# sensor.net
KiCad netlist of a schematic drawn in Altium Designer
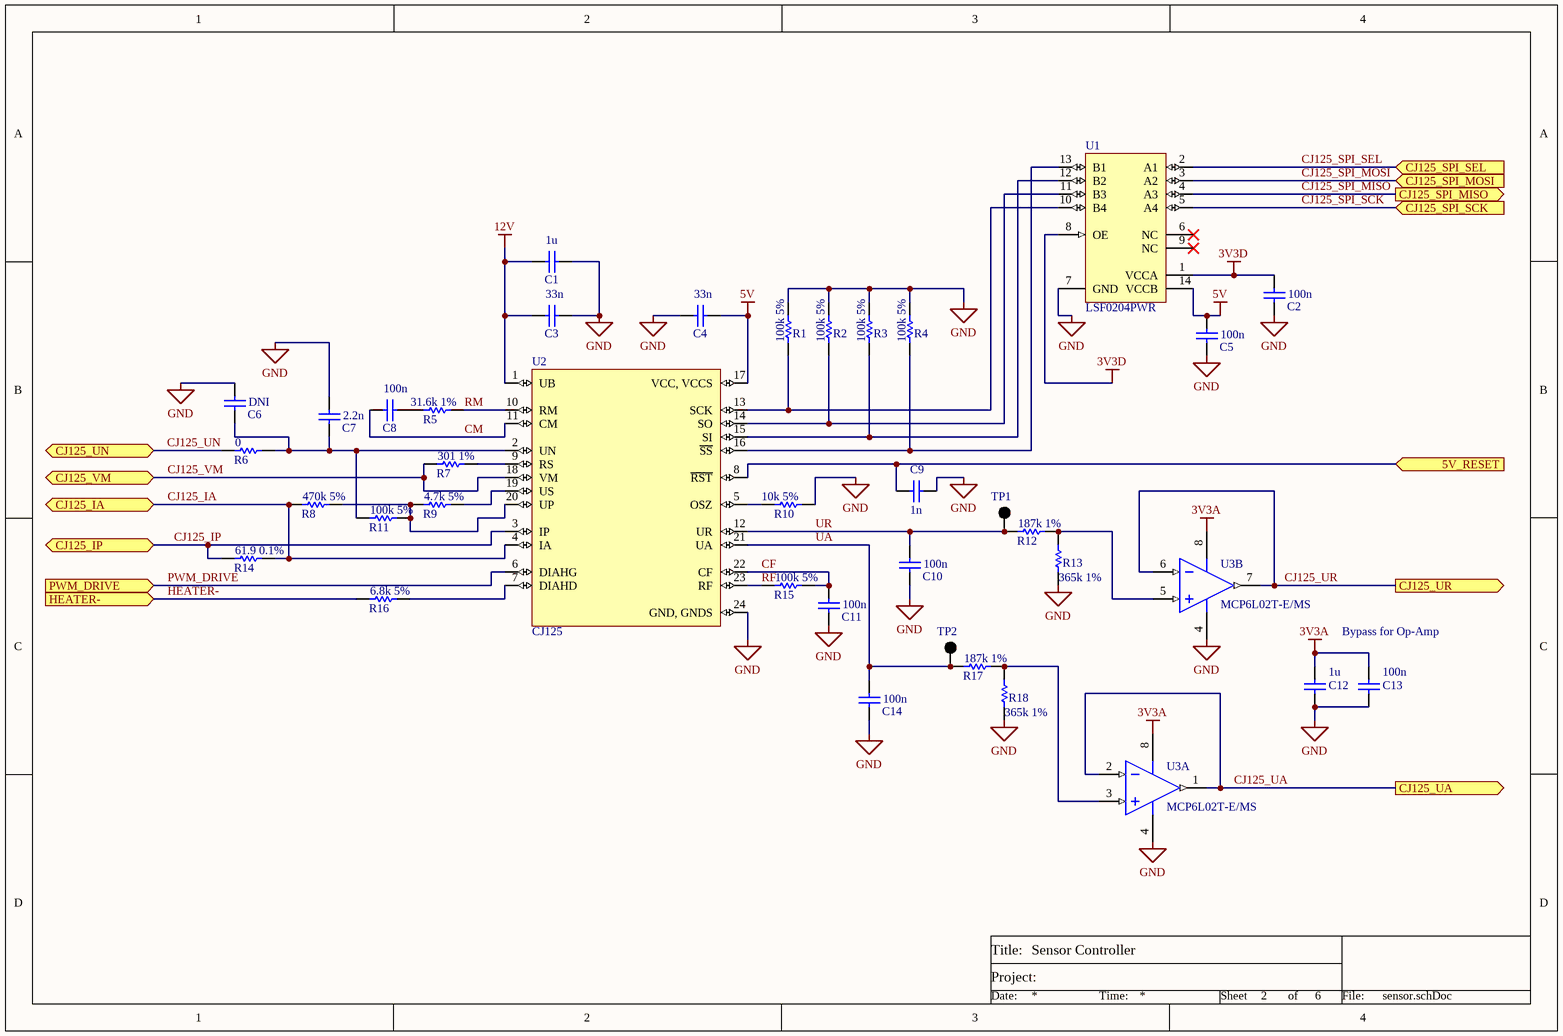
[diagram p0: sensor.schDoc]

(export (version "E")
  (design (tool "Eeschema 10.0.6"))
  (components
    (comp (ref "C1")
      (value "1u")
      (footprint "0805")
      (description "Generic 0805 Capacitor")
      (libsource (lib "symbol_library") (part "C_0805"))
    )
    (comp (ref "C2")
      (value "100n")
      (footprint "0805")
      (description "Generic 0805 Capacitor")
      (libsource (lib "symbol_library") (part "C_0805"))
    )
    (comp (ref "C3")
      (value "33n")
      (footprint "0805")
      (description "Generic 0805 Capacitor")
      (libsource (lib "symbol_library") (part "C_0805"))
    )
    (comp (ref "C4")
      (value "33n")
      (footprint "0805")
      (description "Generic 0805 Capacitor")
      (libsource (lib "symbol_library") (part "C_0805"))
    )
    (comp (ref "C5")
      (value "100n")
      (footprint "0805")
      (description "Generic 0805 Capacitor")
      (libsource (lib "symbol_library") (part "C_0805"))
    )
    (comp (ref "C6")
      (value "DNI")
      (footprint "0805")
      (description "Generic 0805 Capacitor")
      (libsource (lib "symbol_library") (part "C_0805"))
    )
    (comp (ref "C7")
      (value "2.2n")
      (footprint "0805")
      (description "Generic 0805 Capacitor")
      (libsource (lib "symbol_library") (part "C_0805"))
    )
    (comp (ref "C8")
      (value "100n")
      (footprint "0805")
      (description "Generic 0805 Capacitor")
      (libsource (lib "symbol_library") (part "C_0805"))
    )
    (comp (ref "C9")
      (value "1n")
      (footprint "0805")
      (description "Generic 0805 Capacitor")
      (libsource (lib "symbol_library") (part "C_0805"))
    )
    (comp (ref "C10")
      (value "100n")
      (footprint "0805")
      (description "Generic 0805 Capacitor")
      (libsource (lib "symbol_library") (part "C_0805"))
    )
    (comp (ref "C11")
      (value "100n")
      (footprint "0805")
      (description "Generic 0805 Capacitor")
      (libsource (lib "symbol_library") (part "C_0805"))
    )
    (comp (ref "C12")
      (value "1u")
      (footprint "0805")
      (description "Generic 0805 Capacitor")
      (libsource (lib "symbol_library") (part "C_0805"))
    )
    (comp (ref "C13")
      (value "100n")
      (footprint "0805")
      (description "Generic 0805 Capacitor")
      (libsource (lib "symbol_library") (part "C_0805"))
    )
    (comp (ref "C14")
      (value "100n")
      (footprint "0805")
      (description "Generic 0805 Capacitor")
      (libsource (lib "symbol_library") (part "C_0805"))
    )
    (comp (ref "R1")
      (value "100k 5%")
      (footprint "0603")
      (description "Generic 0603 Resistor")
      (libsource (lib "symbol_library") (part "R_0603"))
    )
    (comp (ref "R2")
      (value "100k 5%")
      (footprint "0603")
      (description "Generic 0603 Resistor")
      (libsource (lib "symbol_library") (part "R_0603"))
    )
    (comp (ref "R3")
      (value "100k 5%")
      (footprint "0603")
      (description "Generic 0603 Resistor")
      (libsource (lib "symbol_library") (part "R_0603"))
    )
    (comp (ref "R4")
      (value "100k 5%")
      (footprint "0603")
      (description "Generic 0603 Resistor")
      (libsource (lib "symbol_library") (part "R_0603"))
    )
    (comp (ref "R5")
      (value "31.6k 1%")
      (footprint "0603")
      (description "Generic 0603 Resistor")
      (libsource (lib "symbol_library") (part "R_0603"))
    )
    (comp (ref "R6")
      (value "0")
      (footprint "0603")
      (description "Generic 0603 Resistor")
      (libsource (lib "symbol_library") (part "R_0603"))
    )
    (comp (ref "R7")
      (value "301 1%")
      (footprint "0603")
      (description "Generic 0603 Resistor")
      (libsource (lib "symbol_library") (part "R_0603"))
    )
    (comp (ref "R8")
      (value "470k 5%")
      (footprint "0603")
      (description "Generic 0603 Resistor")
      (libsource (lib "symbol_library") (part "R_0603"))
    )
    (comp (ref "R9")
      (value "4.7k 5%")
      (footprint "0603")
      (description "Generic 0603 Resistor")
      (libsource (lib "symbol_library") (part "R_0603"))
    )
    (comp (ref "R10")
      (value "10k 5%")
      (footprint "0603")
      (description "Generic 0603 Resistor")
      (libsource (lib "symbol_library") (part "R_0603"))
    )
    (comp (ref "R11")
      (value "100k 5%")
      (footprint "0603")
      (description "Generic 0603 Resistor")
      (libsource (lib "symbol_library") (part "R_0603"))
    )
    (comp (ref "R12")
      (value "187k 1%")
      (footprint "0603")
      (description "Generic 0603 Resistor")
      (libsource (lib "symbol_library") (part "R_0603"))
    )
    (comp (ref "R13")
      (value "365k 1%")
      (footprint "0603")
      (description "Generic 0603 Resistor")
      (libsource (lib "symbol_library") (part "R_0603"))
    )
    (comp (ref "R14")
      (value "61.9 0.1%")
      (footprint "0603")
      (description "Generic 0603 Resistor")
      (libsource (lib "symbol_library") (part "R_0603"))
    )
    (comp (ref "R15")
      (value "100k 5%")
      (footprint "0603")
      (description "Generic 0603 Resistor")
      (libsource (lib "symbol_library") (part "R_0603"))
    )
    (comp (ref "R16")
      (value "6.8k 5%")
      (footprint "0603")
      (description "Generic 0603 Resistor")
      (libsource (lib "symbol_library") (part "R_0603"))
    )
    (comp (ref "R17")
      (value "187k 1%")
      (footprint "0603")
      (description "Generic 0603 Resistor")
      (libsource (lib "symbol_library") (part "R_0603"))
    )
    (comp (ref "R18")
      (value "365k 1%")
      (footprint "0603")
      (description "Generic 0603 Resistor")
      (libsource (lib "symbol_library") (part "R_0603"))
    )
    (comp (ref "TP1")
      (value "5001")
      (footprint "KSTN-5001")
      (description "Test Point, Black, 1-Pin THD, RoHS, Bulk")
      (fields (field (name "MANUFACTURER") "Keystone"))
      (libsource (lib "symbol_library") (part "TP5001"))
    )
    (comp (ref "TP2")
      (value "5001")
      (footprint "KSTN-5001")
      (description "Test Point, Black, 1-Pin THD, RoHS, Bulk")
      (fields (field (name "MANUFACTURER") "Keystone"))
      (libsource (lib "symbol_library") (part "TP5001"))
    )
    (comp (ref "U1")
      (value "LSF0204PWR")
      (footprint "PW0014A_M")
      (fields (field (name "MANUFACTURER") "Texas Instruments"))
      (libsource (lib "symbol_library") (part "LSF0204"))
    )
    (comp (ref "U2")
      (value "CJ125")
      (footprint "SOIC-24")
      (description "5V 2Mbaud SMT Lambda Probe Interface IC - SOIC-24")
      (libsource (lib "symbol_library") (part "CJ125"))
    )
    (comp (ref "U3")
      (value "MCP6L02T-E/MS")
      (footprint "MSOP8_M")
      (description "1 MHz, 85 渭A Dual Op Amp, 8-Pin MSOP, Extended Temperature Range, Tape and Reel")
      (libsource (lib "symbol_library") (part "MCP6L02"))
    )
  )
  (nets
    (net (code "1") (name "/5V_RESET") (class "Default")
      (node (ref "C9") (pin "1") (pinfunction "1_1") (pintype "passive"))
      (node (ref "U2") (pin "8") (pinfunction "~{RST}_8") (pintype "bidirectional"))
    )
    (net (code "2") (name "/CF") (class "Default")
      (node (ref "C11") (pin "2") (pinfunction "2_2") (pintype "passive"))
      (node (ref "R15") (pin "2") (pinfunction "2_2") (pintype "passive"))
      (node (ref "U2") (pin "22") (pinfunction "CF_22") (pintype "bidirectional"))
    )
    (net (code "3") (name "/CJ125_IA") (class "Default")
      (node (ref "R14") (pin "2") (pinfunction "2_2") (pintype "passive"))
      (node (ref "R8") (pin "1") (pinfunction "1_1") (pintype "passive"))
      (node (ref "U2") (pin "4") (pinfunction "IA_4") (pintype "bidirectional"))
    )
    (net (code "4") (name "/CJ125_IP") (class "Default")
      (node (ref "R14") (pin "1") (pinfunction "1_1") (pintype "passive"))
      (node (ref "U2") (pin "3") (pinfunction "IP_3") (pintype "bidirectional"))
    )
    (net (code "5") (name "/CJ125_SPI_MISO") (class "Default")
      (node (ref "U1") (pin "4") (pinfunction "A3_4") (pintype "bidirectional"))
    )
    (net (code "6") (name "/CJ125_SPI_MOSI") (class "Default")
      (node (ref "U1") (pin "3") (pinfunction "A2_3") (pintype "bidirectional"))
    )
    (net (code "7") (name "/CJ125_SPI_SCK") (class "Default")
      (node (ref "U1") (pin "5") (pinfunction "A4_5") (pintype "bidirectional"))
    )
    (net (code "8") (name "/CJ125_SPI_SEL") (class "Default")
      (node (ref "U1") (pin "2") (pinfunction "A1_2") (pintype "bidirectional"))
    )
    (net (code "9") (name "/CJ125_UA") (class "Default")
      (node (ref "U3") (pin "1") (pinfunction "VOUTA_1") (pintype "output"))
      (node (ref "U3") (pin "2") (pinfunction "VINA-_2") (pintype "input"))
    )
    (net (code "10") (name "/CJ125_UN") (class "Default")
      (node (ref "R6") (pin "1") (pinfunction "1_1") (pintype "passive"))
    )
    (net (code "11") (name "/CJ125_UR") (class "Default")
      (node (ref "U3") (pin "6") (pinfunction "VINB-_6") (pintype "input"))
      (node (ref "U3") (pin "7") (pinfunction "VOUTB_7") (pintype "output"))
    )
    (net (code "12") (name "/CJ125_VM") (class "Default")
      (node (ref "R7") (pin "1") (pinfunction "1_1") (pintype "passive"))
      (node (ref "U2") (pin "18") (pinfunction "VM_18") (pintype "bidirectional"))
    )
    (net (code "13") (name "/CM") (class "Default")
      (node (ref "C8") (pin "1") (pinfunction "1_1") (pintype "passive"))
      (node (ref "U2") (pin "11") (pinfunction "CM_11") (pintype "bidirectional"))
    )
    (net (code "14") (name "/HEATER-") (class "Default")
      (node (ref "R16") (pin "1") (pinfunction "1_1") (pintype "passive"))
    )
    (net (code "15") (name "/PWM_DRIVE") (class "Default")
      (node (ref "U2") (pin "6") (pinfunction "DIAHG_6") (pintype "bidirectional"))
    )
    (net (code "16") (name "/RF") (class "Default")
      (node (ref "R15") (pin "1") (pinfunction "1_1") (pintype "passive"))
      (node (ref "U2") (pin "23") (pinfunction "RF_23") (pintype "bidirectional"))
    )
    (net (code "17") (name "/RM") (class "Default")
      (node (ref "R5") (pin "2") (pinfunction "2_2") (pintype "passive"))
      (node (ref "U2") (pin "10") (pinfunction "RM_10") (pintype "bidirectional"))
    )
    (net (code "18") (name "/UA") (class "Default")
      (node (ref "C14") (pin "2") (pinfunction "2_2") (pintype "passive"))
      (node (ref "R17") (pin "1") (pinfunction "1_1") (pintype "passive"))
      (node (ref "TP2") (pin "1") (pintype "passive"))
      (node (ref "U2") (pin "21") (pinfunction "UA_21") (pintype "bidirectional"))
    )
    (net (code "19") (name "/UR") (class "Default")
      (node (ref "C10") (pin "2") (pinfunction "2_2") (pintype "passive"))
      (node (ref "R12") (pin "1") (pinfunction "1_1") (pintype "passive"))
      (node (ref "TP1") (pin "1") (pintype "passive"))
      (node (ref "U2") (pin "12") (pinfunction "UR_12") (pintype "bidirectional"))
    )
    (net (code "20") (name "3V3A") (class "Default")
      (node (ref "C12") (pin "2") (pinfunction "2_2") (pintype "passive"))
      (node (ref "C13") (pin "2") (pinfunction "2_2") (pintype "passive"))
      (node (ref "U3") (pin "8") (pinfunction "VDD_8") (pintype "power_in"))
    )
    (net (code "21") (name "3V3D") (class "Default")
      (node (ref "C2") (pin "2") (pinfunction "2_2") (pintype "passive"))
      (node (ref "U1") (pin "1") (pinfunction "VCCA_1") (pintype "power_in"))
      (node (ref "U1") (pin "8") (pinfunction "OE_8") (pintype "input"))
    )
    (net (code "22") (name "5V") (class "Default")
      (node (ref "C4") (pin "1") (pinfunction "1_1") (pintype "passive"))
      (node (ref "C5") (pin "2") (pinfunction "2_2") (pintype "passive"))
      (node (ref "U1") (pin "14") (pinfunction "VCCB_14") (pintype "power_in"))
      (node (ref "U2") (pin "17") (pinfunction "VCC,_VCCS_17") (pintype "bidirectional"))
    )
    (net (code "23") (name "12V") (class "Default")
      (node (ref "C1") (pin "1") (pinfunction "1_1") (pintype "passive"))
      (node (ref "C3") (pin "2") (pinfunction "2_2") (pintype "passive"))
      (node (ref "U2") (pin "1") (pinfunction "UB_1") (pintype "bidirectional"))
    )
    (net (code "24") (name "GND") (class "Default")
      (node (ref "C1") (pin "2") (pinfunction "2_2") (pintype "passive"))
      (node (ref "C10") (pin "1") (pinfunction "1_1") (pintype "passive"))
      (node (ref "C11") (pin "1") (pinfunction "1_1") (pintype "passive"))
      (node (ref "C12") (pin "1") (pinfunction "1_1") (pintype "passive"))
      (node (ref "C13") (pin "1") (pinfunction "1_1") (pintype "passive"))
      (node (ref "C14") (pin "1") (pinfunction "1_1") (pintype "passive"))
      (node (ref "C2") (pin "1") (pinfunction "1_1") (pintype "passive"))
      (node (ref "C3") (pin "1") (pinfunction "1_1") (pintype "passive"))
      (node (ref "C4") (pin "2") (pinfunction "2_2") (pintype "passive"))
      (node (ref "C5") (pin "1") (pinfunction "1_1") (pintype "passive"))
      (node (ref "C6") (pin "2") (pinfunction "2_2") (pintype "passive"))
      (node (ref "C7") (pin "2") (pinfunction "2_2") (pintype "passive"))
      (node (ref "C9") (pin "2") (pinfunction "2_2") (pintype "passive"))
      (node (ref "R1") (pin "2") (pinfunction "2_2") (pintype "passive"))
      (node (ref "R10") (pin "2") (pinfunction "2_2") (pintype "passive"))
      (node (ref "R13") (pin "1") (pinfunction "1_1") (pintype "passive"))
      (node (ref "R18") (pin "1") (pinfunction "1_1") (pintype "passive"))
      (node (ref "R2") (pin "2") (pinfunction "2_2") (pintype "passive"))
      (node (ref "R3") (pin "2") (pinfunction "2_2") (pintype "passive"))
      (node (ref "R4") (pin "2") (pinfunction "2_2") (pintype "passive"))
      (node (ref "U1") (pin "7") (pinfunction "GND_7") (pintype "power_in"))
      (node (ref "U2") (pin "24") (pinfunction "GND,_GNDS_24") (pintype "bidirectional"))
      (node (ref "U3") (pin "4") (pinfunction "VSS_4") (pintype "power_in"))
    )
    (net (code "25") (name "Net-(C8-Pad2)") (class "Default")
      (node (ref "C8") (pin "2") (pinfunction "2_2") (pintype "passive"))
      (node (ref "R5") (pin "1") (pinfunction "1_1") (pintype "passive"))
    )
    (net (code "26") (name "Net-(U1-B1)") (class "Default")
      (node (ref "R4") (pin "1") (pinfunction "1_1") (pintype "passive"))
      (node (ref "U1") (pin "13") (pinfunction "B1_13") (pintype "bidirectional"))
      (node (ref "U2") (pin "16") (pinfunction "~{SS}_16") (pintype "bidirectional"))
    )
    (net (code "27") (name "Net-(U1-B2)") (class "Default")
      (node (ref "R3") (pin "1") (pinfunction "1_1") (pintype "passive"))
      (node (ref "U1") (pin "12") (pinfunction "B2_12") (pintype "bidirectional"))
      (node (ref "U2") (pin "15") (pinfunction "SI_15") (pintype "bidirectional"))
    )
    (net (code "28") (name "Net-(U1-B3)") (class "Default")
      (node (ref "R2") (pin "1") (pinfunction "1_1") (pintype "passive"))
      (node (ref "U1") (pin "11") (pinfunction "B3_11") (pintype "bidirectional"))
      (node (ref "U2") (pin "14") (pinfunction "SO_14") (pintype "bidirectional"))
    )
    (net (code "29") (name "Net-(U1-B4)") (class "Default")
      (node (ref "R1") (pin "1") (pinfunction "1_1") (pintype "passive"))
      (node (ref "U1") (pin "10") (pinfunction "B4_10") (pintype "bidirectional"))
      (node (ref "U2") (pin "13") (pinfunction "SCK_13") (pintype "bidirectional"))
    )
    (net (code "30") (name "Net-(U2-DIAHD)") (class "Default")
      (node (ref "R16") (pin "2") (pinfunction "2_2") (pintype "passive"))
      (node (ref "U2") (pin "7") (pinfunction "DIAHD_7") (pintype "bidirectional"))
    )
    (net (code "31") (name "Net-(U2-OSZ)") (class "Default")
      (node (ref "R10") (pin "1") (pinfunction "1_1") (pintype "passive"))
      (node (ref "U2") (pin "5") (pinfunction "OSZ_5") (pintype "bidirectional"))
    )
    (net (code "32") (name "Net-(U2-RS)") (class "Default")
      (node (ref "R7") (pin "2") (pinfunction "2_2") (pintype "passive"))
      (node (ref "U2") (pin "9") (pinfunction "RS_9") (pintype "bidirectional"))
    )
    (net (code "33") (name "Net-(U2-UN)") (class "Default")
      (node (ref "C6") (pin "1") (pinfunction "1_1") (pintype "passive"))
      (node (ref "C7") (pin "1") (pinfunction "1_1") (pintype "passive"))
      (node (ref "R11") (pin "1") (pinfunction "1_1") (pintype "passive"))
      (node (ref "R6") (pin "2") (pinfunction "2_2") (pintype "passive"))
      (node (ref "U2") (pin "2") (pinfunction "UN_2") (pintype "bidirectional"))
    )
    (net (code "34") (name "Net-(U2-UP)") (class "Default")
      (node (ref "R11") (pin "2") (pinfunction "2_2") (pintype "passive"))
      (node (ref "R8") (pin "2") (pinfunction "2_2") (pintype "passive"))
      (node (ref "R9") (pin "1") (pinfunction "1_1") (pintype "passive"))
      (node (ref "U2") (pin "20") (pinfunction "UP_20") (pintype "bidirectional"))
    )
    (net (code "35") (name "Net-(U2-US)") (class "Default")
      (node (ref "R9") (pin "2") (pinfunction "2_2") (pintype "passive"))
      (node (ref "U2") (pin "19") (pinfunction "US_19") (pintype "bidirectional"))
    )
    (net (code "36") (name "Net-(U3A-VINA+)") (class "Default")
      (node (ref "R17") (pin "2") (pinfunction "2_2") (pintype "passive"))
      (node (ref "R18") (pin "2") (pinfunction "2_2") (pintype "passive"))
      (node (ref "U3") (pin "3") (pinfunction "VINA+_3") (pintype "input"))
    )
    (net (code "37") (name "Net-(U3B-VINB+)") (class "Default")
      (node (ref "R12") (pin "2") (pinfunction "2_2") (pintype "passive"))
      (node (ref "R13") (pin "2") (pinfunction "2_2") (pintype "passive"))
      (node (ref "U3") (pin "5") (pinfunction "VINB+_5") (pintype "input"))
    )
    (net (code "38") (name "unconnected-(U1-NC-Pad6)") (class "Default")
      (node (ref "U1") (pin "6") (pinfunction "NC_6") (pintype "passive+no_connect"))
    )
    (net (code "39") (name "unconnected-(U1-NC-Pad9)") (class "Default")
      (node (ref "U1") (pin "9") (pinfunction "NC_9") (pintype "passive+no_connect"))
    )
  )
)
